# teensy-jst_01_2_v7.net
KiCad netlist of a schematic drawn in EAGLE
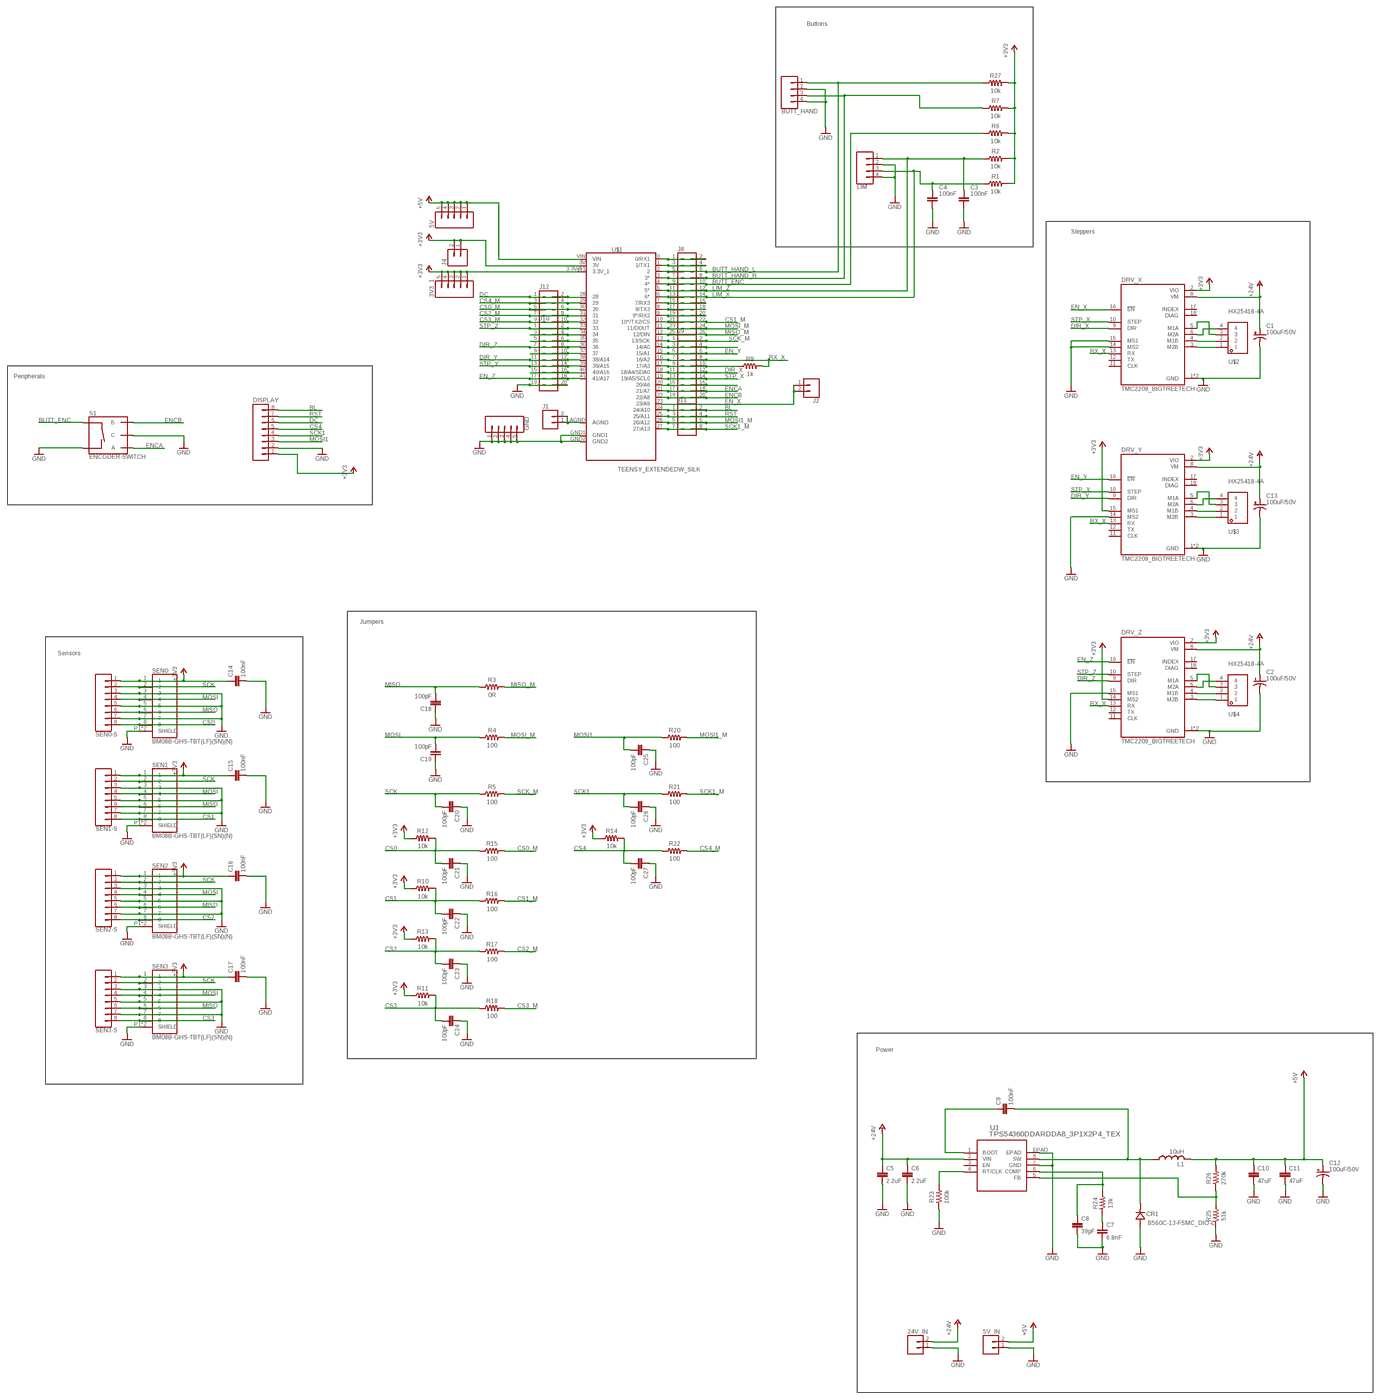
[diagram p0: schematic, sheet 1, overview]
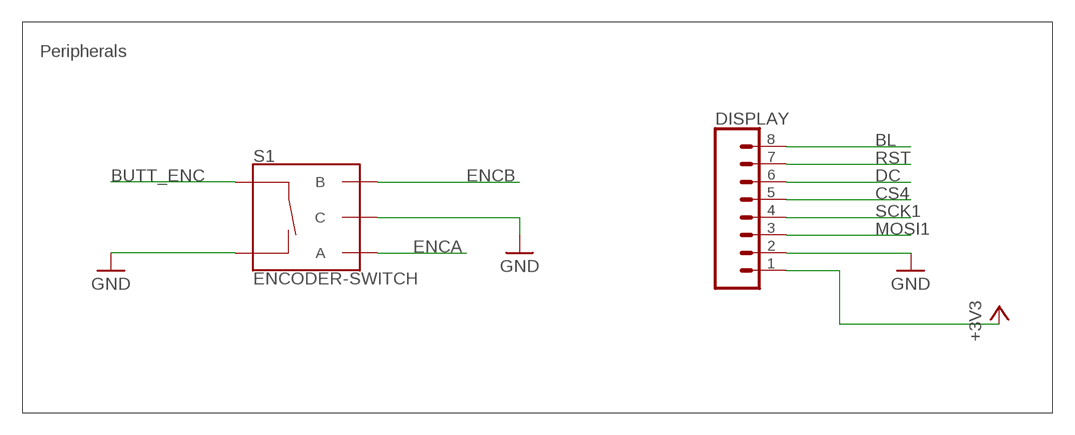
[diagram p1: schematic, sheet 1, part 1 of 4]
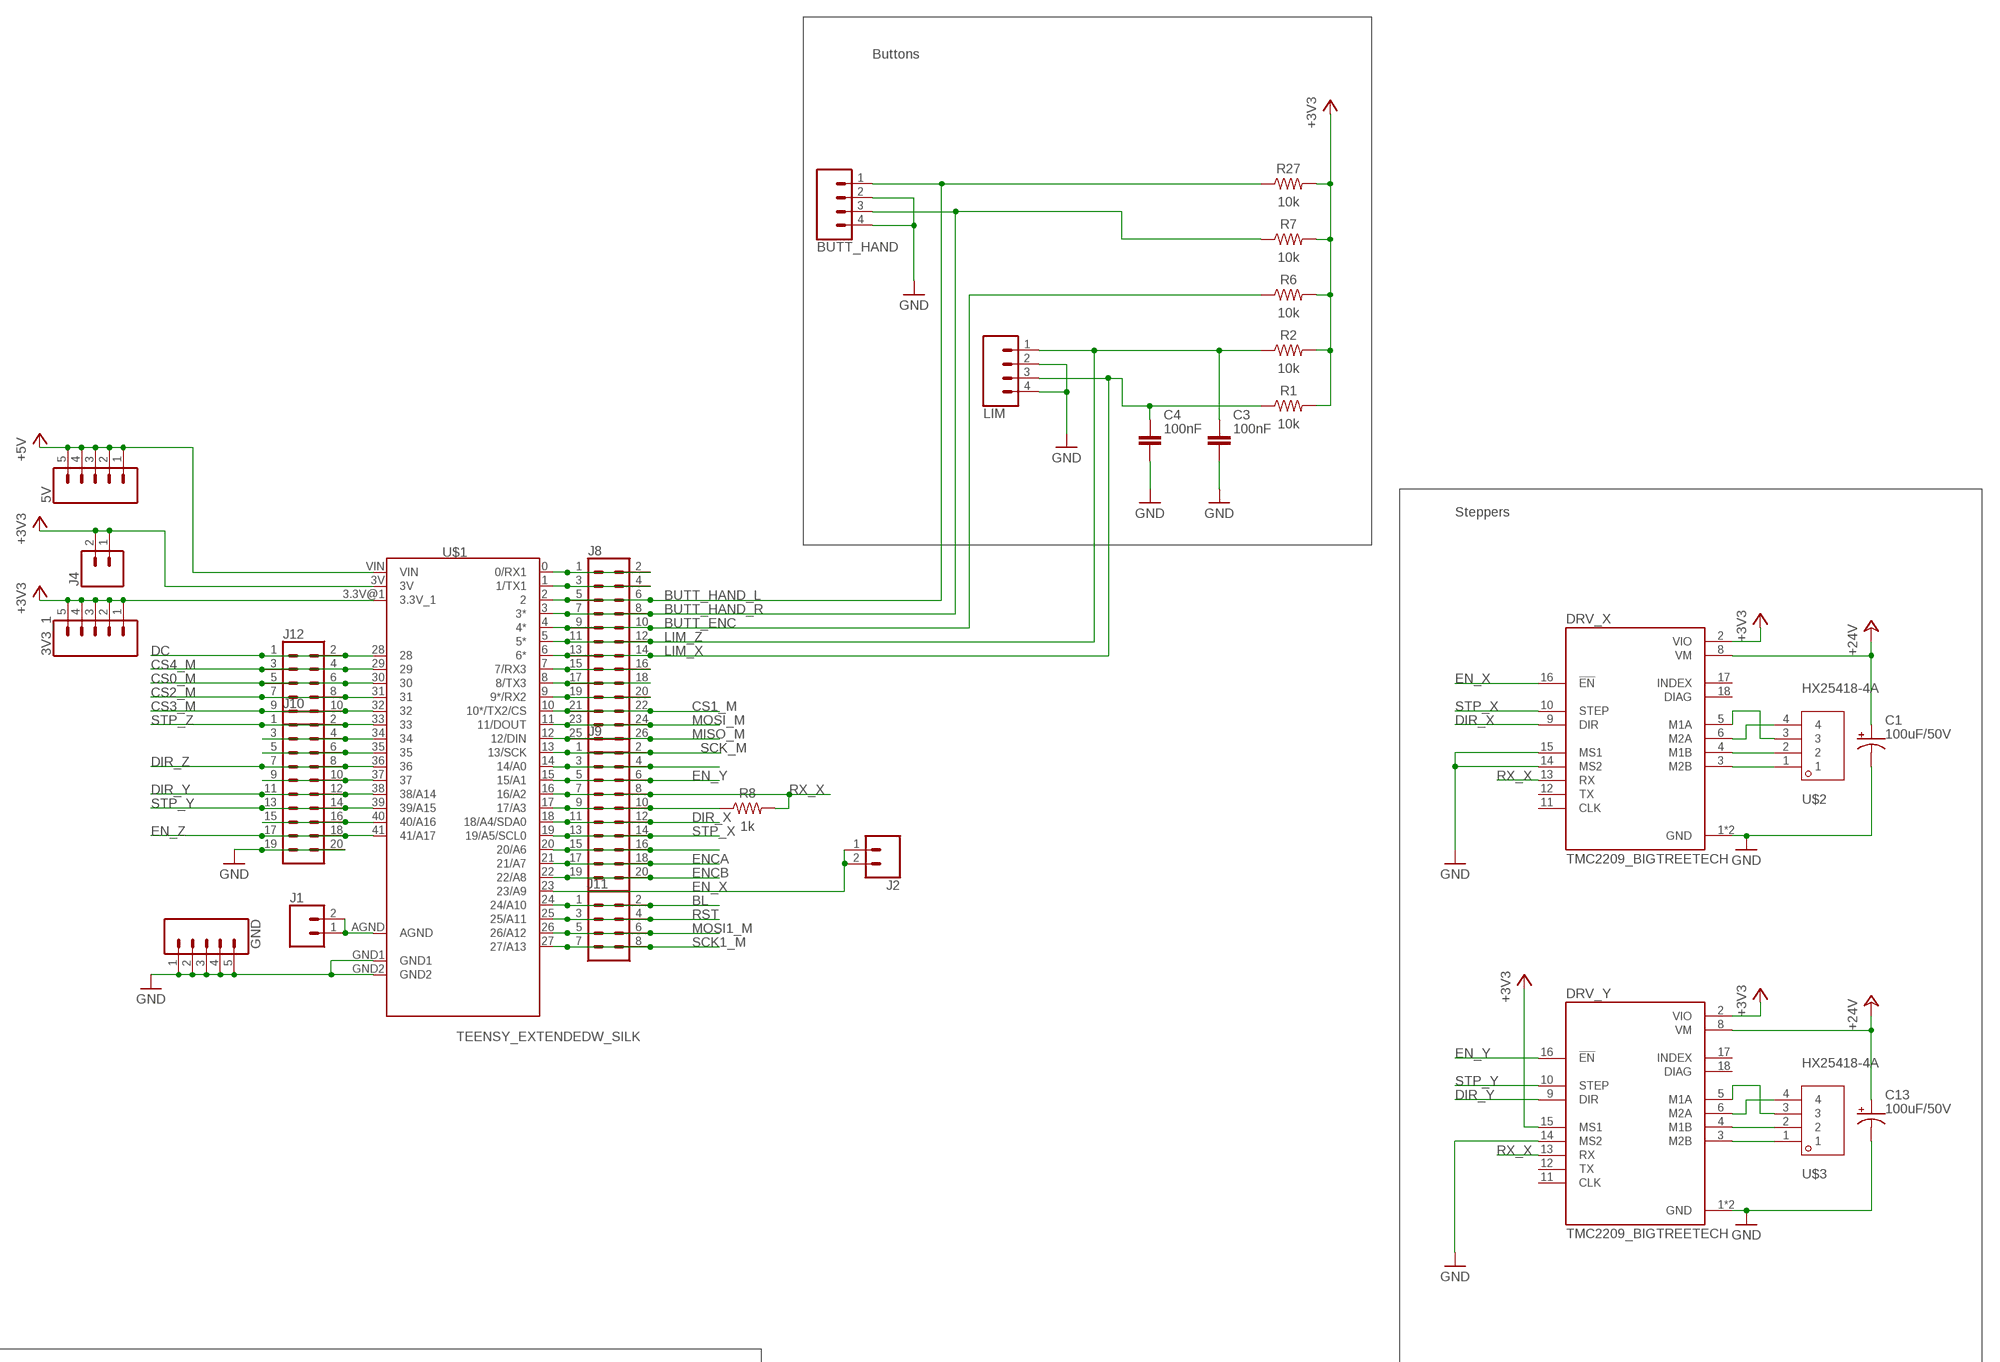
[diagram p2: schematic, sheet 1, part 2 of 4]
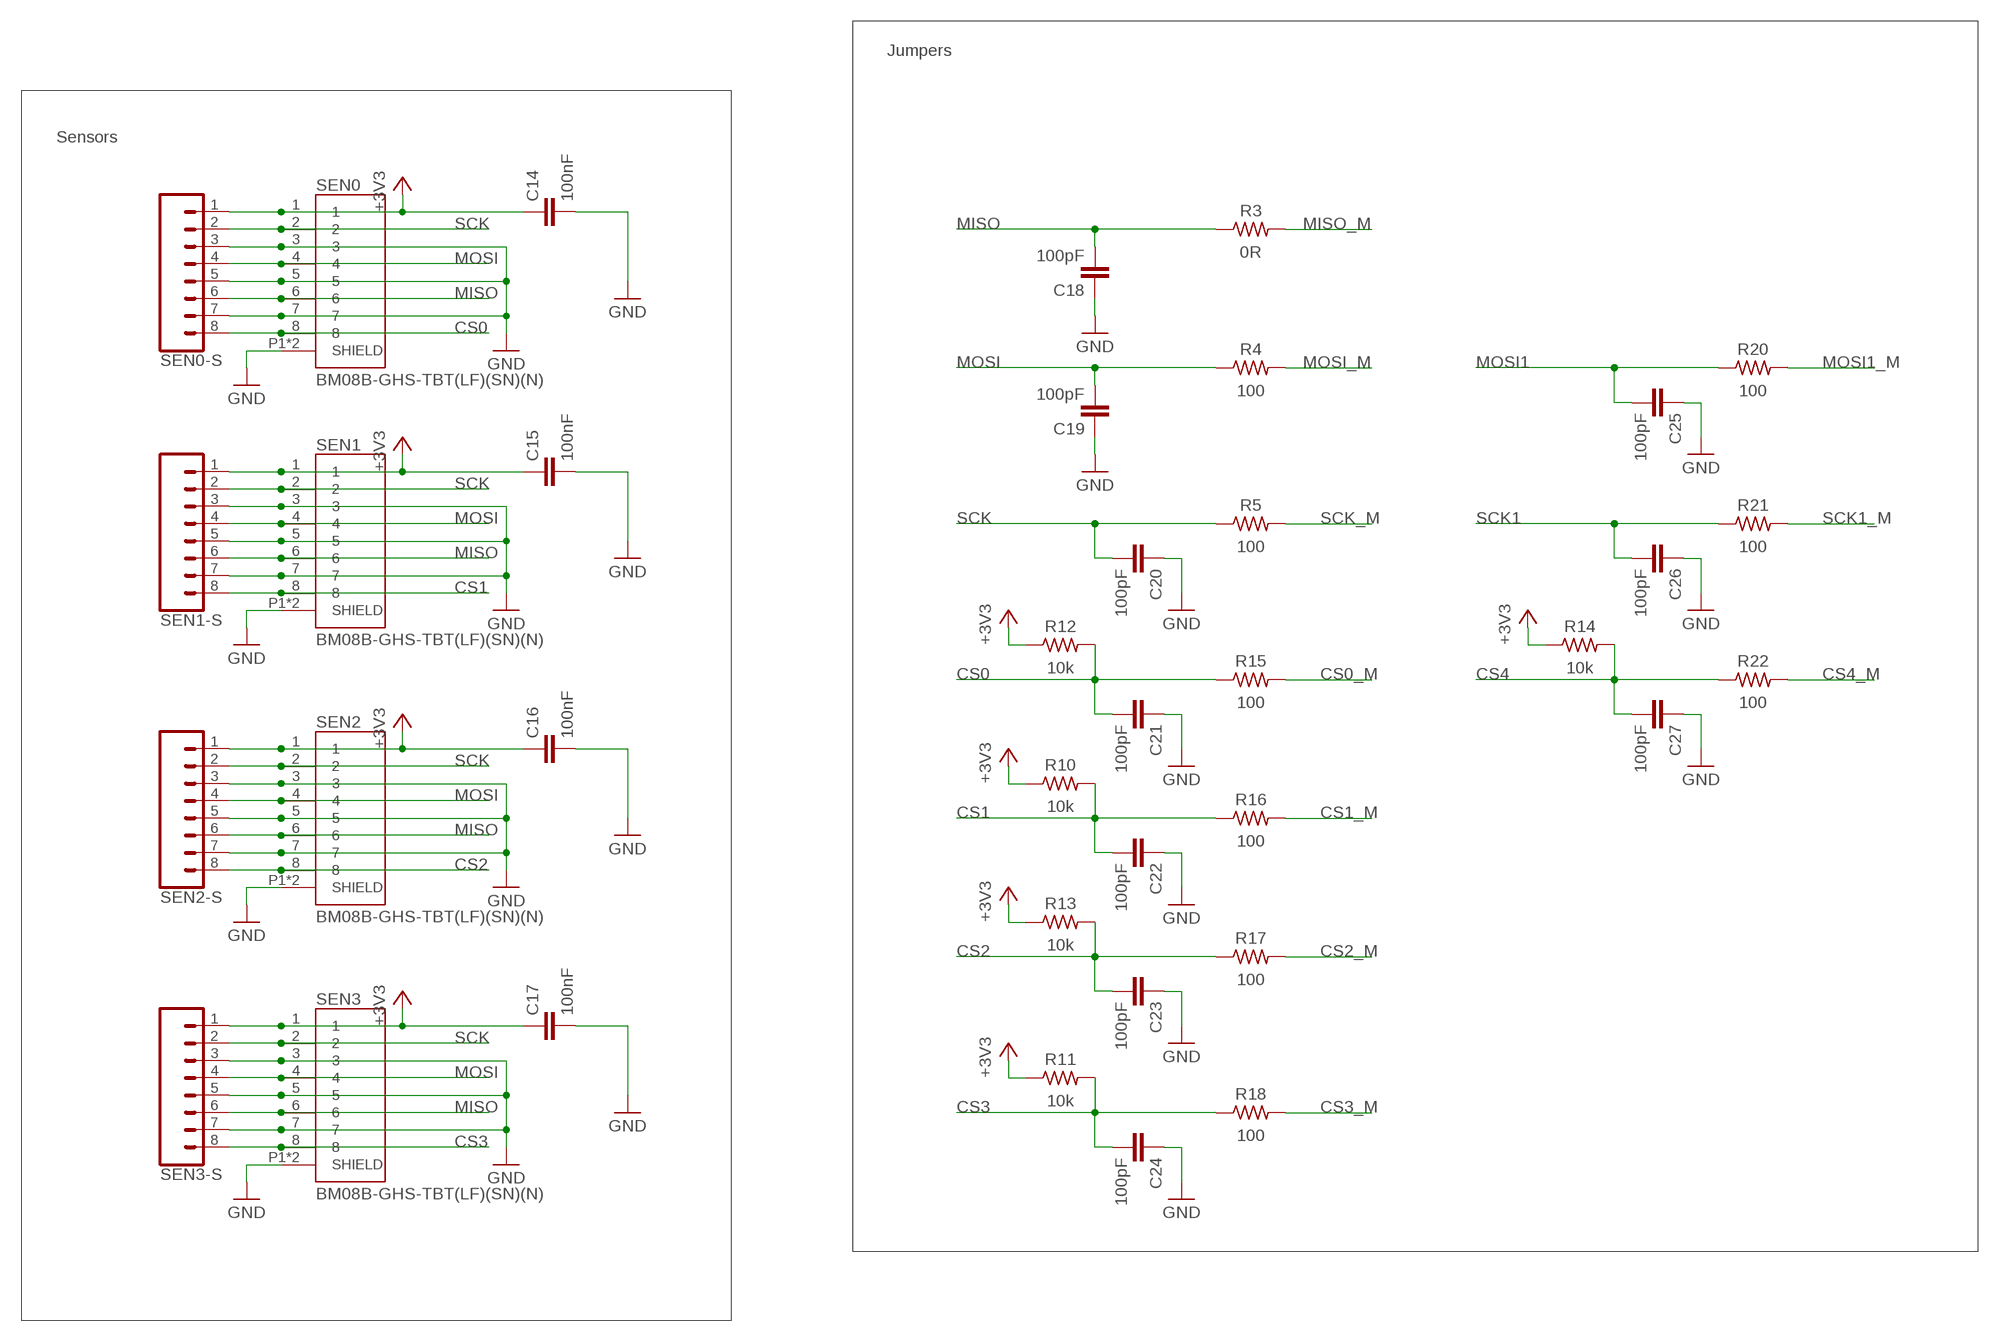
[diagram p3: schematic, sheet 1, part 3 of 4]
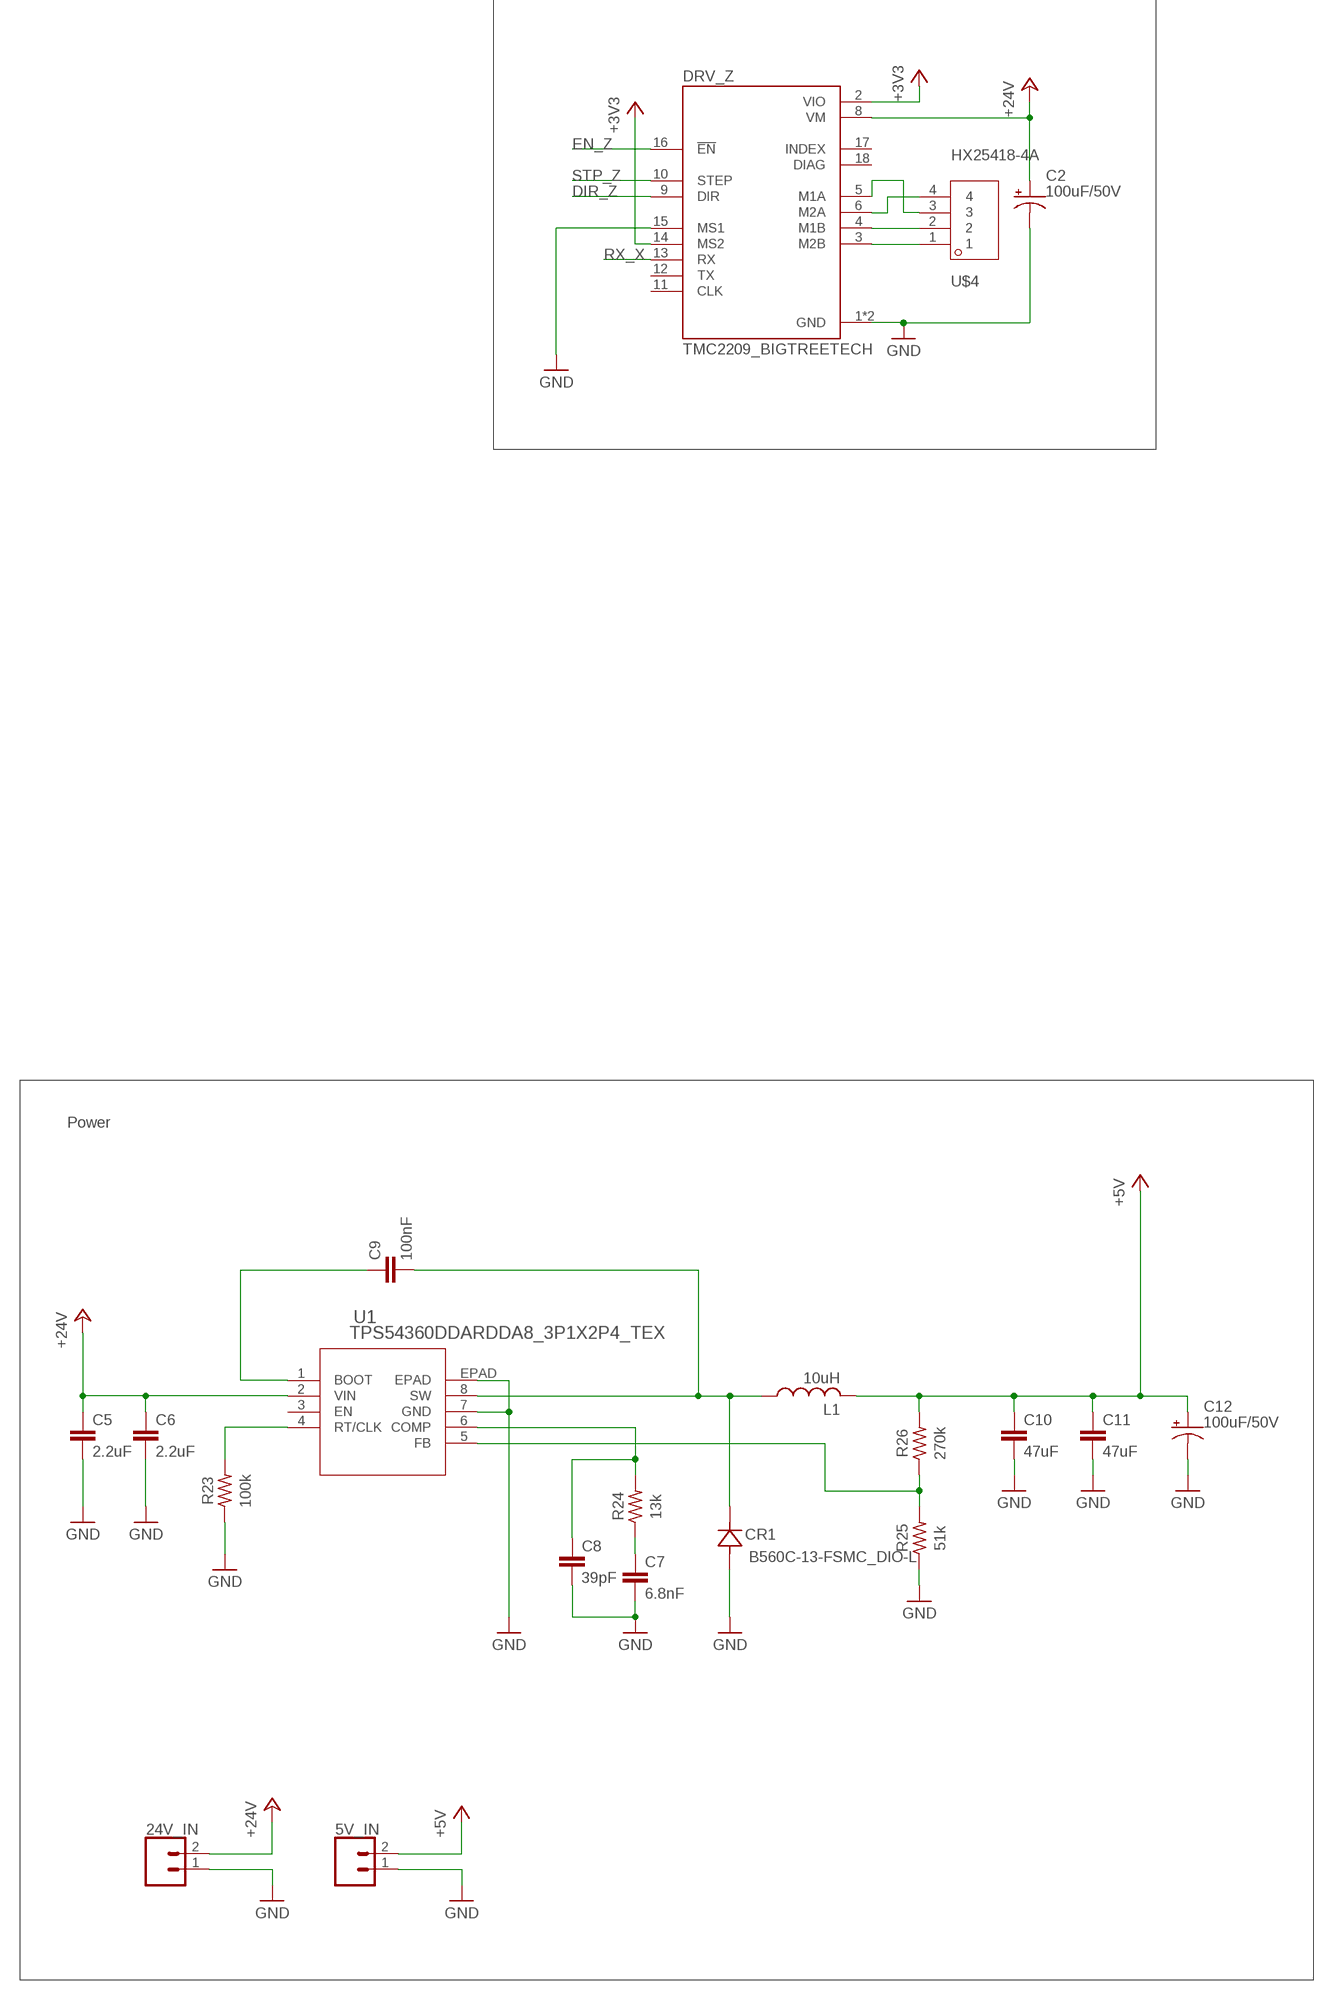
[diagram p4: schematic, sheet 1, part 4 of 4]

(export (version "E")
  (design (tool "Eeschema 10.0.6"))
  (components
    (comp (ref "3V3_1")
      (value "CONN_05PTH")
      (footprint "eagle-import:1X05")
      (libsource (lib "eagle-import") (part "CONN_05PTH"))
    )
    (comp (ref "5V")
      (value "CONN_05PTH")
      (footprint "eagle-import:1X05")
      (libsource (lib "eagle-import") (part "CONN_05PTH"))
    )
    (comp (ref "5V_IN")
      (value "CONN_025MM")
      (footprint "eagle-import:SCREWTERMINAL-5MM-2")
      (libsource (lib "eagle-import") (part "CONN_025MM"))
    )
    (comp (ref "24V_IN")
      (value "CONN_025MM")
      (footprint "eagle-import:SCREWTERMINAL-5MM-2")
      (libsource (lib "eagle-import") (part "CONN_025MM"))
    )
    (comp (ref "BUTT_HAND")
      (value "CONN_041X04_NO_SILK")
      (footprint "eagle-import:1X04_NO_SILK")
      (libsource (lib "eagle-import") (part "CONN_041X04_NO_SILK"))
    )
    (comp (ref "C1")
      (value "100uF/50V")
      (footprint "eagle-import:PANASONIC_D")
      (libsource (lib "eagle-import") (part "CPOL-USD"))
    )
    (comp (ref "C2")
      (value "100uF/50V")
      (footprint "eagle-import:PANASONIC_D")
      (libsource (lib "eagle-import") (part "CPOL-USD"))
    )
    (comp (ref "C3")
      (value "100nF")
      (footprint "eagle-import:C0603")
      (libsource (lib "eagle-import") (part "C-EUC0603"))
    )
    (comp (ref "C4")
      (value "100nF")
      (footprint "eagle-import:C0603")
      (libsource (lib "eagle-import") (part "C-EUC0603"))
    )
    (comp (ref "C5")
      (value "2.2uF")
      (footprint "eagle-import:C0603")
      (libsource (lib "eagle-import") (part "C-EUC0603"))
    )
    (comp (ref "C6")
      (value "2.2uF")
      (footprint "eagle-import:C0603")
      (libsource (lib "eagle-import") (part "C-EUC0603"))
    )
    (comp (ref "C7")
      (value "6.8nF")
      (footprint "eagle-import:C0402")
      (libsource (lib "eagle-import") (part "C-EUC0402"))
    )
    (comp (ref "C8")
      (value "39pF")
      (footprint "eagle-import:C0402")
      (libsource (lib "eagle-import") (part "C-EUC0402"))
    )
    (comp (ref "C9")
      (value "100nF")
      (footprint "eagle-import:C0402")
      (libsource (lib "eagle-import") (part "C-EUC0402"))
    )
    (comp (ref "C10")
      (value "47uF")
      (footprint "eagle-import:C0603")
      (libsource (lib "eagle-import") (part "C-EUC0603"))
    )
    (comp (ref "C11")
      (value "47uF")
      (footprint "eagle-import:C0603")
      (libsource (lib "eagle-import") (part "C-EUC0603"))
    )
    (comp (ref "C12")
      (value "100uF/50V")
      (footprint "eagle-import:PANASONIC_D")
      (libsource (lib "eagle-import") (part "CPOL-USD"))
    )
    (comp (ref "C13")
      (value "100uF/50V")
      (footprint "eagle-import:PANASONIC_D")
      (libsource (lib "eagle-import") (part "CPOL-USD"))
    )
    (comp (ref "C14")
      (value "100nF")
      (footprint "eagle-import:C0402")
      (libsource (lib "eagle-import") (part "C-EUC0402"))
    )
    (comp (ref "C15")
      (value "100nF")
      (footprint "eagle-import:C0402")
      (libsource (lib "eagle-import") (part "C-EUC0402"))
    )
    (comp (ref "C16")
      (value "100nF")
      (footprint "eagle-import:C0402")
      (libsource (lib "eagle-import") (part "C-EUC0402"))
    )
    (comp (ref "C17")
      (value "100nF")
      (footprint "eagle-import:C0402")
      (libsource (lib "eagle-import") (part "C-EUC0402"))
    )
    (comp (ref "C18")
      (value "100pF")
      (footprint "eagle-import:C0402K")
      (libsource (lib "eagle-import") (part "C-EUC0402K"))
    )
    (comp (ref "C19")
      (value "100pF")
      (footprint "eagle-import:C0402K")
      (libsource (lib "eagle-import") (part "C-EUC0402K"))
    )
    (comp (ref "C20")
      (value "100pF")
      (footprint "eagle-import:C0402K")
      (libsource (lib "eagle-import") (part "C-EUC0402K"))
    )
    (comp (ref "C21")
      (value "100pF")
      (footprint "eagle-import:C0402K")
      (libsource (lib "eagle-import") (part "C-EUC0402K"))
    )
    (comp (ref "C22")
      (value "100pF")
      (footprint "eagle-import:C0402")
      (libsource (lib "eagle-import") (part "C-EUC0402"))
    )
    (comp (ref "C23")
      (value "100pF")
      (footprint "eagle-import:C0402K")
      (libsource (lib "eagle-import") (part "C-EUC0402K"))
    )
    (comp (ref "C24")
      (value "100pF")
      (footprint "eagle-import:C0402K")
      (libsource (lib "eagle-import") (part "C-EUC0402K"))
    )
    (comp (ref "C25")
      (value "100pF")
      (footprint "eagle-import:C0402K")
      (libsource (lib "eagle-import") (part "C-EUC0402K"))
    )
    (comp (ref "C26")
      (value "100pF")
      (footprint "eagle-import:C0402K")
      (libsource (lib "eagle-import") (part "C-EUC0402K"))
    )
    (comp (ref "C27")
      (value "100pF")
      (footprint "eagle-import:C0402K")
      (libsource (lib "eagle-import") (part "C-EUC0402K"))
    )
    (comp (ref "CR1")
      (value "B560C-13-FSMC_DIO-L")
      (footprint "eagle-import:SMC_DIO-L")
      (fields
        (field (name "MANUFACTURER_PART_NUMBER") "B560C-13-F")
        (field (name "COPYRIGHT") "Copyright (C) 2024 Ultra Librarian. All rights reserved.")
      )
      (libsource (lib "eagle-import") (part "B560C-13-FSMC_DIO-L"))
    )
    (comp (ref "DISPLAY")
      (value "CONN_08\"")
      (footprint "eagle-import:1X08")
      (libsource (lib "eagle-import") (part "CONN_08{dblquote}"))
    )
    (comp (ref "DRV_X")
      (value "TMC2209_BIGTREETECH")
      (footprint "eagle-import:MODULE_TMC2209_BIGTREETECH")
      (fields
        (field (name "MF") "Trinamic Motion Control GmbH")
        (field (name "MP") "TMC2209 SILENTSTEPSTICK")
      )
      (libsource (lib "eagle-import") (part "TMC2209_BIGTREETECH"))
    )
    (comp (ref "DRV_Y")
      (value "TMC2209_BIGTREETECH")
      (footprint "eagle-import:MODULE_TMC2209_BIGTREETECH")
      (fields
        (field (name "MF") "Trinamic Motion Control GmbH")
        (field (name "MP") "TMC2209 SILENTSTEPSTICK")
      )
      (libsource (lib "eagle-import") (part "TMC2209_BIGTREETECH"))
    )
    (comp (ref "DRV_Z")
      (value "TMC2209_BIGTREETECH")
      (footprint "eagle-import:MODULE_TMC2209_BIGTREETECH")
      (fields
        (field (name "MF") "Trinamic Motion Control GmbH")
        (field (name "MP") "TMC2209 SILENTSTEPSTICK")
      )
      (libsource (lib "eagle-import") (part "TMC2209_BIGTREETECH"))
    )
    (comp (ref "GND")
      (value "CONN_05PTH")
      (footprint "eagle-import:1X05")
      (libsource (lib "eagle-import") (part "CONN_05PTH"))
    )
    (comp (ref "J1")
      (value "CONN_02")
      (footprint "eagle-import:1X02")
      (libsource (lib "eagle-import") (part "CONN_02"))
    )
    (comp (ref "J2")
      (value "CONN_02")
      (footprint "eagle-import:1X02")
      (libsource (lib "eagle-import") (part "CONN_02"))
    )
    (comp (ref "J4")
      (value "CONN_02")
      (footprint "eagle-import:1X02")
      (libsource (lib "eagle-import") (part "CONN_02"))
    )
    (comp (ref "J8")
      (value "CONN_13X22X13")
      (footprint "eagle-import:2X13")
      (libsource (lib "eagle-import") (part "CONN_13X22X13"))
    )
    (comp (ref "J9")
      (value "CONN_10X2")
      (footprint "eagle-import:2X10")
      (libsource (lib "eagle-import") (part "CONN_10X2"))
    )
    (comp (ref "J10")
      (value "CONN_10X2")
      (footprint "eagle-import:2X10")
      (libsource (lib "eagle-import") (part "CONN_10X2"))
    )
    (comp (ref "J11")
      (value "CONN_04X2")
      (footprint "eagle-import:2X4")
      (libsource (lib "eagle-import") (part "CONN_04X2"))
    )
    (comp (ref "J12")
      (value "CONN_05X2PTH")
      (footprint "eagle-import:2X5")
      (libsource (lib "eagle-import") (part "CONN_05X2PTH"))
    )
    (comp (ref "L1")
      (value "10uH")
      (footprint "eagle-import:MWSA0503S-100MT")
      (libsource (lib "eagle-import") (part "L-USMWSA0503S-100MT"))
    )
    (comp (ref "LIM")
      (value "CONN_041X04_NO_SILK")
      (footprint "eagle-import:1X04_NO_SILK")
      (libsource (lib "eagle-import") (part "CONN_041X04_NO_SILK"))
    )
    (comp (ref "R1")
      (value "10k")
      (footprint "eagle-import:RESC1608X60")
      (libsource (lib "eagle-import") (part "R-USCHIP-0603(1608-METRIC)_"))
    )
    (comp (ref "R2")
      (value "10k")
      (footprint "eagle-import:RESC1608X60")
      (libsource (lib "eagle-import") (part "R-USCHIP-0603(1608-METRIC)_"))
    )
    (comp (ref "R3")
      (value "0R")
      (footprint "eagle-import:RESC1608X60")
      (libsource (lib "eagle-import") (part "R-USCHIP-0603(1608-METRIC)_"))
    )
    (comp (ref "R4")
      (value "100")
      (footprint "eagle-import:RESC1608X60")
      (libsource (lib "eagle-import") (part "R-USCHIP-0603(1608-METRIC)_"))
    )
    (comp (ref "R5")
      (value "100")
      (footprint "eagle-import:RESC1608X60")
      (libsource (lib "eagle-import") (part "R-USCHIP-0603(1608-METRIC)_"))
    )
    (comp (ref "R6")
      (value "10k")
      (footprint "eagle-import:RESC1608X60")
      (libsource (lib "eagle-import") (part "R-USCHIP-0603(1608-METRIC)_"))
    )
    (comp (ref "R7")
      (value "10k")
      (footprint "eagle-import:RESC1608X60")
      (libsource (lib "eagle-import") (part "R-USCHIP-0603(1608-METRIC)_"))
    )
    (comp (ref "R8")
      (value "1k")
      (footprint "eagle-import:RESC1608X60")
      (libsource (lib "eagle-import") (part "R-USCHIP-0603(1608-METRIC)_"))
    )
    (comp (ref "R10")
      (value "10k")
      (footprint "eagle-import:RESC1608X60")
      (libsource (lib "eagle-import") (part "R-USCHIP-0603(1608-METRIC)_"))
    )
    (comp (ref "R11")
      (value "10k")
      (footprint "eagle-import:RESC1608X60")
      (libsource (lib "eagle-import") (part "R-USCHIP-0603(1608-METRIC)_"))
    )
    (comp (ref "R12")
      (value "10k")
      (footprint "eagle-import:RESC1608X60")
      (libsource (lib "eagle-import") (part "R-USCHIP-0603(1608-METRIC)_"))
    )
    (comp (ref "R13")
      (value "10k")
      (footprint "eagle-import:RESC1608X60")
      (libsource (lib "eagle-import") (part "R-USCHIP-0603(1608-METRIC)_"))
    )
    (comp (ref "R14")
      (value "10k")
      (footprint "eagle-import:RESC1608X60")
      (libsource (lib "eagle-import") (part "R-USCHIP-0603(1608-METRIC)_"))
    )
    (comp (ref "R15")
      (value "100")
      (footprint "eagle-import:RESC1608X60")
      (libsource (lib "eagle-import") (part "R-USCHIP-0603(1608-METRIC)_"))
    )
    (comp (ref "R16")
      (value "100")
      (footprint "eagle-import:RESC1608X60")
      (libsource (lib "eagle-import") (part "R-USCHIP-0603(1608-METRIC)_"))
    )
    (comp (ref "R17")
      (value "100")
      (footprint "eagle-import:RESC1608X60")
      (libsource (lib "eagle-import") (part "R-USCHIP-0603(1608-METRIC)_"))
    )
    (comp (ref "R18")
      (value "100")
      (footprint "eagle-import:RESC1608X60")
      (libsource (lib "eagle-import") (part "R-USCHIP-0603(1608-METRIC)_"))
    )
    (comp (ref "R20")
      (value "100")
      (footprint "eagle-import:RESC1608X60")
      (libsource (lib "eagle-import") (part "R-USCHIP-0603(1608-METRIC)_"))
    )
    (comp (ref "R21")
      (value "100")
      (footprint "eagle-import:RESC1608X60")
      (libsource (lib "eagle-import") (part "R-USCHIP-0603(1608-METRIC)_"))
    )
    (comp (ref "R22")
      (value "100")
      (footprint "eagle-import:RESC1608X60")
      (libsource (lib "eagle-import") (part "R-USCHIP-0603(1608-METRIC)_"))
    )
    (comp (ref "R23")
      (value "100k")
      (footprint "eagle-import:RESC1005X40")
      (libsource (lib "eagle-import") (part "R-USCHIP-0402(1005-METRIC)_"))
    )
    (comp (ref "R24")
      (value "13k")
      (footprint "eagle-import:RESC1005X40")
      (libsource (lib "eagle-import") (part "R-USCHIP-0402(1005-METRIC)_"))
    )
    (comp (ref "R25")
      (value "51k")
      (footprint "eagle-import:RESC1005X40")
      (libsource (lib "eagle-import") (part "R-USCHIP-0402(1005-METRIC)_"))
    )
    (comp (ref "R26")
      (value "270k")
      (footprint "eagle-import:RESC1005X40")
      (libsource (lib "eagle-import") (part "R-USCHIP-0402(1005-METRIC)_"))
    )
    (comp (ref "R27")
      (value "10k")
      (footprint "eagle-import:RESC1608X60")
      (libsource (lib "eagle-import") (part "R-USCHIP-0603(1608-METRIC)_"))
    )
    (comp (ref "S1")
      (value "ENCODER-SWITCH")
      (footprint "eagle-import:ROTARY_ENC_PLAIN")
      (libsource (lib "eagle-import") (part "ENCODER-SWITCH"))
    )
    (comp (ref "SEN0")
      (value "BM08B-GHS-TBT(LF)(SN)(N)")
      (footprint "eagle-import:JST_BM08B-GHS-TBT(LF)(SN)(N)")
      (fields (field (name "MF") "JST Sales"))
      (libsource (lib "eagle-import") (part "BM08B-GHS-TBT(LF)(SN)(N)"))
    )
    (comp (ref "SEN0-S")
      (value "CONN_08\"")
      (footprint "eagle-import:1X08")
      (libsource (lib "eagle-import") (part "CONN_08{dblquote}"))
    )
    (comp (ref "SEN1")
      (value "BM08B-GHS-TBT(LF)(SN)(N)")
      (footprint "eagle-import:JST_BM08B-GHS-TBT(LF)(SN)(N)")
      (fields (field (name "MF") "JST Sales"))
      (libsource (lib "eagle-import") (part "BM08B-GHS-TBT(LF)(SN)(N)"))
    )
    (comp (ref "SEN1-S")
      (value "CONN_08\"")
      (footprint "eagle-import:1X08")
      (libsource (lib "eagle-import") (part "CONN_08{dblquote}"))
    )
    (comp (ref "SEN2")
      (value "BM08B-GHS-TBT(LF)(SN)(N)")
      (footprint "eagle-import:JST_BM08B-GHS-TBT(LF)(SN)(N)")
      (fields (field (name "MF") "JST Sales"))
      (libsource (lib "eagle-import") (part "BM08B-GHS-TBT(LF)(SN)(N)"))
    )
    (comp (ref "SEN2-S")
      (value "CONN_08\"")
      (footprint "eagle-import:1X08")
      (libsource (lib "eagle-import") (part "CONN_08{dblquote}"))
    )
    (comp (ref "SEN3")
      (value "BM08B-GHS-TBT(LF)(SN)(N)")
      (footprint "eagle-import:JST_BM08B-GHS-TBT(LF)(SN)(N)")
      (fields (field (name "MF") "JST Sales"))
      (libsource (lib "eagle-import") (part "BM08B-GHS-TBT(LF)(SN)(N)"))
    )
    (comp (ref "SEN3-S")
      (value "CONN_08\"")
      (footprint "eagle-import:1X08")
      (libsource (lib "eagle-import") (part "CONN_08{dblquote}"))
    )
    (comp (ref "U$1")
      (value "TEENSY_EXTENDEDW_SILK")
      (footprint "eagle-import:TEENSY_EXTENDED")
      (libsource (lib "eagle-import") (part "TEENSY_EXTENDEDW_SILK"))
    )
    (comp (ref "U$2")
      (value "HX25418-4A")
      (footprint "eagle-import:HX25418-4A")
      (libsource (lib "eagle-import") (part "HX25418-4A"))
    )
    (comp (ref "U$3")
      (value "HX25418-4A")
      (footprint "eagle-import:HX25418-4A")
      (libsource (lib "eagle-import") (part "HX25418-4A"))
    )
    (comp (ref "U$4")
      (value "HX25418-4A")
      (footprint "eagle-import:HX25418-4A")
      (libsource (lib "eagle-import") (part "HX25418-4A"))
    )
    (comp (ref "U1")
      (value "TPS54360DDARDDA8_3P1X2P4_TEX")
      (footprint "eagle-import:DDA8_3P1X2P4_TEX")
      (fields
        (field (name "MANUFACTURER_PART_NUMBER") "TPS54360DDAR")
        (field (name "COPYRIGHT") "Copyright (C) 2024 Ultra Librarian. All rights reserved.")
      )
      (libsource (lib "eagle-import") (part "TPS54360DDARDDA8_3P1X2P4_TEX"))
    )
  )
  (nets
    (net (code "1") (name "+3V3") (class "Default")
      (node (ref "3V3_1") (pin "1") (pinfunction "1_1") (pintype "passive"))
      (node (ref "3V3_1") (pin "2") (pinfunction "2_2") (pintype "passive"))
      (node (ref "3V3_1") (pin "3") (pinfunction "3_3") (pintype "passive"))
      (node (ref "3V3_1") (pin "4") (pinfunction "4_4") (pintype "passive"))
      (node (ref "3V3_1") (pin "5") (pinfunction "5_5") (pintype "passive"))
      (node (ref "C14") (pin "1") (pinfunction "1_1") (pintype "passive"))
      (node (ref "C15") (pin "1") (pinfunction "1_1") (pintype "passive"))
      (node (ref "C16") (pin "1") (pinfunction "1_1") (pintype "passive"))
      (node (ref "C17") (pin "1") (pinfunction "1_1") (pintype "passive"))
      (node (ref "DISPLAY") (pin "1") (pinfunction "1_1") (pintype "passive"))
      (node (ref "DRV_X") (pin "2") (pinfunction "VIO_2") (pintype "power_in"))
      (node (ref "DRV_Y") (pin "15") (pinfunction "MS1_15") (pintype "input"))
      (node (ref "DRV_Y") (pin "2") (pinfunction "VIO_2") (pintype "power_in"))
      (node (ref "DRV_Z") (pin "14") (pinfunction "MS2_14") (pintype "input"))
      (node (ref "DRV_Z") (pin "2") (pinfunction "VIO_2") (pintype "power_in"))
      (node (ref "J4") (pin "1") (pinfunction "1_1") (pintype "passive"))
      (node (ref "J4") (pin "2") (pinfunction "2_2") (pintype "passive"))
      (node (ref "R1") (pin "2") (pinfunction "2_2") (pintype "passive"))
      (node (ref "R10") (pin "1") (pinfunction "1_1") (pintype "passive"))
      (node (ref "R11") (pin "1") (pinfunction "1_1") (pintype "passive"))
      (node (ref "R12") (pin "1") (pinfunction "1_1") (pintype "passive"))
      (node (ref "R13") (pin "1") (pinfunction "1_1") (pintype "passive"))
      (node (ref "R14") (pin "1") (pinfunction "1_1") (pintype "passive"))
      (node (ref "R2") (pin "2") (pinfunction "2_2") (pintype "passive"))
      (node (ref "R27") (pin "2") (pinfunction "2_2") (pintype "passive"))
      (node (ref "R6") (pin "2") (pinfunction "2_2") (pintype "passive"))
      (node (ref "R7") (pin "2") (pinfunction "2_2") (pintype "passive"))
      (node (ref "SEN0") (pin "1") (pinfunction "1_1") (pintype "passive"))
      (node (ref "SEN0-S") (pin "1") (pinfunction "1_1") (pintype "passive"))
      (node (ref "SEN1") (pin "1") (pinfunction "1_1") (pintype "passive"))
      (node (ref "SEN1-S") (pin "1") (pinfunction "1_1") (pintype "passive"))
      (node (ref "SEN2") (pin "1") (pinfunction "1_1") (pintype "passive"))
      (node (ref "SEN2-S") (pin "1") (pinfunction "1_1") (pintype "passive"))
      (node (ref "SEN3") (pin "1") (pinfunction "1_1") (pintype "passive"))
      (node (ref "SEN3-S") (pin "1") (pinfunction "1_1") (pintype "passive"))
      (node (ref "U$1") (pin "3.3V@1") (pinfunction "3.3V_1_3.3V@1") (pintype "power_in"))
      (node (ref "U$1") (pin "3V") (pinfunction "3V_3V") (pintype "power_in"))
    )
    (net (code "2") (name "+5V") (class "Default")
      (node (ref "5V") (pin "1") (pinfunction "1_1") (pintype "passive"))
      (node (ref "5V") (pin "2") (pinfunction "2_2") (pintype "passive"))
      (node (ref "5V") (pin "3") (pinfunction "3_3") (pintype "passive"))
      (node (ref "5V") (pin "4") (pinfunction "4_4") (pintype "passive"))
      (node (ref "5V") (pin "5") (pinfunction "5_5") (pintype "passive"))
      (node (ref "5V_IN") (pin "2") (pinfunction "2_2") (pintype "passive"))
      (node (ref "C10") (pin "1") (pinfunction "1_1") (pintype "passive"))
      (node (ref "C11") (pin "1") (pinfunction "1_1") (pintype "passive"))
      (node (ref "C12") (pin "+") (pinfunction "+_+") (pintype "passive"))
      (node (ref "L1") (pin "2") (pinfunction "2_2") (pintype "passive"))
      (node (ref "R26") (pin "2") (pinfunction "2_2") (pintype "passive"))
      (node (ref "U$1") (pin "VIN") (pinfunction "VIN_VIN") (pintype "power_in"))
    )
    (net (code "3") (name "+24V") (class "Default")
      (node (ref "24V_IN") (pin "2") (pinfunction "2_2") (pintype "passive"))
      (node (ref "C1") (pin "+") (pinfunction "+_+") (pintype "passive"))
      (node (ref "C13") (pin "+") (pinfunction "+_+") (pintype "passive"))
      (node (ref "C2") (pin "+") (pinfunction "+_+") (pintype "passive"))
      (node (ref "C5") (pin "1") (pinfunction "1_1") (pintype "passive"))
      (node (ref "C6") (pin "1") (pinfunction "1_1") (pintype "passive"))
      (node (ref "DRV_X") (pin "8") (pinfunction "VM_8") (pintype "power_in"))
      (node (ref "DRV_Y") (pin "8") (pinfunction "VM_8") (pintype "power_in"))
      (node (ref "DRV_Z") (pin "8") (pinfunction "VM_8") (pintype "power_in"))
      (node (ref "U1") (pin "2") (pinfunction "VIN_2") (pintype "input"))
    )
    (net (code "4") (name "/BL") (class "Default")
      (node (ref "DISPLAY") (pin "8") (pinfunction "8_8") (pintype "passive"))
      (node (ref "J11") (pin "1") (pinfunction "1_1") (pintype "passive"))
      (node (ref "J11") (pin "2") (pinfunction "2_2") (pintype "passive"))
      (node (ref "U$1") (pin "24") (pinfunction "24/A10_24") (pintype "bidirectional"))
    )
    (net (code "5") (name "/BUTT_ENC") (class "Default")
      (node (ref "J8") (pin "10") (pinfunction "10_10") (pintype "passive"))
      (node (ref "J8") (pin "9") (pinfunction "9_9") (pintype "passive"))
      (node (ref "R6") (pin "1") (pinfunction "1_1") (pintype "passive"))
      (node (ref "S1") (pin "SW+") (pinfunction "SW+_SW+") (pintype "bidirectional"))
      (node (ref "U$1") (pin "4") (pinfunction "4*_4") (pintype "bidirectional"))
    )
    (net (code "6") (name "/BUTT_HAND_L") (class "Default")
      (node (ref "BUTT_HAND") (pin "1") (pinfunction "1_1") (pintype "passive"))
      (node (ref "J8") (pin "5") (pinfunction "5_5") (pintype "passive"))
      (node (ref "J8") (pin "6") (pinfunction "6_6") (pintype "passive"))
      (node (ref "R27") (pin "1") (pinfunction "1_1") (pintype "passive"))
      (node (ref "U$1") (pin "2") (pinfunction "2_2") (pintype "bidirectional"))
    )
    (net (code "7") (name "/BUTT_HAND_R") (class "Default")
      (node (ref "BUTT_HAND") (pin "3") (pinfunction "3_3") (pintype "passive"))
      (node (ref "J8") (pin "7") (pinfunction "7_7") (pintype "passive"))
      (node (ref "J8") (pin "8") (pinfunction "8_8") (pintype "passive"))
      (node (ref "R7") (pin "1") (pinfunction "1_1") (pintype "passive"))
      (node (ref "U$1") (pin "3") (pinfunction "3*_3") (pintype "bidirectional"))
    )
    (net (code "8") (name "/CS0") (class "Default")
      (node (ref "C21") (pin "2") (pinfunction "2_2") (pintype "passive"))
      (node (ref "R12") (pin "2") (pinfunction "2_2") (pintype "passive"))
      (node (ref "R15") (pin "1") (pinfunction "1_1") (pintype "passive"))
      (node (ref "SEN0") (pin "8") (pinfunction "8_8") (pintype "passive"))
      (node (ref "SEN0-S") (pin "8") (pinfunction "8_8") (pintype "passive"))
    )
    (net (code "9") (name "/CS0_M") (class "Default")
      (node (ref "J12") (pin "5") (pinfunction "5_5") (pintype "passive"))
      (node (ref "J12") (pin "6") (pinfunction "6_6") (pintype "passive"))
      (node (ref "R15") (pin "2") (pinfunction "2_2") (pintype "passive"))
      (node (ref "U$1") (pin "30") (pinfunction "30_30") (pintype "bidirectional"))
    )
    (net (code "10") (name "/CS1") (class "Default")
      (node (ref "C22") (pin "2") (pinfunction "2_2") (pintype "passive"))
      (node (ref "R10") (pin "2") (pinfunction "2_2") (pintype "passive"))
      (node (ref "R16") (pin "1") (pinfunction "1_1") (pintype "passive"))
      (node (ref "SEN1") (pin "8") (pinfunction "8_8") (pintype "passive"))
      (node (ref "SEN1-S") (pin "8") (pinfunction "8_8") (pintype "passive"))
    )
    (net (code "11") (name "/CS1_M") (class "Default")
      (node (ref "J8") (pin "21") (pinfunction "21_21") (pintype "passive"))
      (node (ref "J8") (pin "22") (pinfunction "22_22") (pintype "passive"))
      (node (ref "R16") (pin "2") (pinfunction "2_2") (pintype "passive"))
      (node (ref "U$1") (pin "10") (pinfunction "10*/TX2/CS_10") (pintype "bidirectional"))
    )
    (net (code "12") (name "/CS2") (class "Default")
      (node (ref "C23") (pin "2") (pinfunction "2_2") (pintype "passive"))
      (node (ref "R13") (pin "2") (pinfunction "2_2") (pintype "passive"))
      (node (ref "R17") (pin "1") (pinfunction "1_1") (pintype "passive"))
      (node (ref "SEN2") (pin "8") (pinfunction "8_8") (pintype "passive"))
      (node (ref "SEN2-S") (pin "8") (pinfunction "8_8") (pintype "passive"))
    )
    (net (code "13") (name "/CS2_M") (class "Default")
      (node (ref "J12") (pin "7") (pinfunction "7_7") (pintype "passive"))
      (node (ref "J12") (pin "8") (pinfunction "8_8") (pintype "passive"))
      (node (ref "R17") (pin "2") (pinfunction "2_2") (pintype "passive"))
      (node (ref "U$1") (pin "31") (pinfunction "31_31") (pintype "bidirectional"))
    )
    (net (code "14") (name "/CS3") (class "Default")
      (node (ref "C24") (pin "2") (pinfunction "2_2") (pintype "passive"))
      (node (ref "R11") (pin "2") (pinfunction "2_2") (pintype "passive"))
      (node (ref "R18") (pin "1") (pinfunction "1_1") (pintype "passive"))
      (node (ref "SEN3") (pin "8") (pinfunction "8_8") (pintype "passive"))
      (node (ref "SEN3-S") (pin "8") (pinfunction "8_8") (pintype "passive"))
    )
    (net (code "15") (name "/CS3_M") (class "Default")
      (node (ref "J12") (pin "10") (pinfunction "10_10") (pintype "passive"))
      (node (ref "J12") (pin "9") (pinfunction "9_9") (pintype "passive"))
      (node (ref "R18") (pin "2") (pinfunction "2_2") (pintype "passive"))
      (node (ref "U$1") (pin "32") (pinfunction "32_32") (pintype "bidirectional"))
    )
    (net (code "16") (name "/CS4") (class "Default")
      (node (ref "C27") (pin "2") (pinfunction "2_2") (pintype "passive"))
      (node (ref "DISPLAY") (pin "5") (pinfunction "5_5") (pintype "passive"))
      (node (ref "R14") (pin "2") (pinfunction "2_2") (pintype "passive"))
      (node (ref "R22") (pin "1") (pinfunction "1_1") (pintype "passive"))
    )
    (net (code "17") (name "/CS4_M") (class "Default")
      (node (ref "J12") (pin "3") (pinfunction "3_3") (pintype "passive"))
      (node (ref "J12") (pin "4") (pinfunction "4_4") (pintype "passive"))
      (node (ref "R22") (pin "2") (pinfunction "2_2") (pintype "passive"))
      (node (ref "U$1") (pin "29") (pinfunction "29_29") (pintype "bidirectional"))
    )
    (net (code "18") (name "/DC") (class "Default")
      (node (ref "DISPLAY") (pin "6") (pinfunction "6_6") (pintype "passive"))
      (node (ref "J12") (pin "1") (pinfunction "1_1") (pintype "passive"))
      (node (ref "J12") (pin "2") (pinfunction "2_2") (pintype "passive"))
      (node (ref "U$1") (pin "28") (pinfunction "28_28") (pintype "bidirectional"))
    )
    (net (code "19") (name "/DIR_X") (class "Default")
      (node (ref "DRV_X") (pin "9") (pinfunction "DIR_9") (pintype "input"))
      (node (ref "J9") (pin "11") (pinfunction "11_11") (pintype "passive"))
      (node (ref "J9") (pin "12") (pinfunction "12_12") (pintype "passive"))
      (node (ref "U$1") (pin "18") (pinfunction "18/A4/SDA0_18") (pintype "bidirectional"))
    )
    (net (code "20") (name "/DIR_Y") (class "Default")
      (node (ref "DRV_Y") (pin "9") (pinfunction "DIR_9") (pintype "input"))
      (node (ref "J10") (pin "11") (pinfunction "11_11") (pintype "passive"))
      (node (ref "J10") (pin "12") (pinfunction "12_12") (pintype "passive"))
      (node (ref "U$1") (pin "38") (pinfunction "38/A14_38") (pintype "bidirectional"))
    )
    (net (code "21") (name "/DIR_Z") (class "Default")
      (node (ref "DRV_Z") (pin "9") (pinfunction "DIR_9") (pintype "input"))
      (node (ref "J10") (pin "7") (pinfunction "7_7") (pintype "passive"))
      (node (ref "J10") (pin "8") (pinfunction "8_8") (pintype "passive"))
      (node (ref "U$1") (pin "36") (pinfunction "36_36") (pintype "bidirectional"))
    )
    (net (code "22") (name "/ENCA") (class "Default")
      (node (ref "J9") (pin "17") (pinfunction "17_17") (pintype "passive"))
      (node (ref "J9") (pin "18") (pinfunction "18_18") (pintype "passive"))
      (node (ref "S1") (pin "A") (pinfunction "A_A") (pintype "bidirectional"))
      (node (ref "U$1") (pin "21") (pinfunction "21/A7_21") (pintype "bidirectional"))
    )
    (net (code "23") (name "/ENCB") (class "Default")
      (node (ref "J9") (pin "19") (pinfunction "19_19") (pintype "passive"))
      (node (ref "J9") (pin "20") (pinfunction "20_20") (pintype "passive"))
      (node (ref "S1") (pin "B") (pinfunction "B_B") (pintype "bidirectional"))
      (node (ref "U$1") (pin "22") (pinfunction "22/A8_22") (pintype "bidirectional"))
    )
    (net (code "24") (name "/EN_X") (class "Default")
      (node (ref "DRV_X") (pin "16") (pinfunction "~{EN}_16") (pintype "input"))
      (node (ref "J2") (pin "1") (pinfunction "1_1") (pintype "passive"))
      (node (ref "J2") (pin "2") (pinfunction "2_2") (pintype "passive"))
      (node (ref "U$1") (pin "23") (pinfunction "23/A9_23") (pintype "bidirectional"))
    )
    (net (code "25") (name "/EN_Y") (class "Default")
      (node (ref "DRV_Y") (pin "16") (pinfunction "~{EN}_16") (pintype "input"))
      (node (ref "J9") (pin "5") (pinfunction "5_5") (pintype "passive"))
      (node (ref "J9") (pin "6") (pinfunction "6_6") (pintype "passive"))
      (node (ref "U$1") (pin "15") (pinfunction "15/A1_15") (pintype "bidirectional"))
    )
    (net (code "26") (name "/EN_Z") (class "Default")
      (node (ref "DRV_Z") (pin "16") (pinfunction "~{EN}_16") (pintype "input"))
      (node (ref "J10") (pin "17") (pinfunction "17_17") (pintype "passive"))
      (node (ref "J10") (pin "18") (pinfunction "18_18") (pintype "passive"))
      (node (ref "U$1") (pin "41") (pinfunction "41/A17_41") (pintype "bidirectional"))
    )
    (net (code "27") (name "/LIM_X") (class "Default")
      (node (ref "C4") (pin "1") (pinfunction "1_1") (pintype "passive"))
      (node (ref "J8") (pin "13") (pinfunction "13_13") (pintype "passive"))
      (node (ref "J8") (pin "14") (pinfunction "14_14") (pintype "passive"))
      (node (ref "LIM") (pin "3") (pinfunction "3_3") (pintype "passive"))
      (node (ref "R1") (pin "1") (pinfunction "1_1") (pintype "passive"))
      (node (ref "U$1") (pin "6") (pinfunction "6*_6") (pintype "bidirectional"))
    )
    (net (code "28") (name "/LIM_Z") (class "Default")
      (node (ref "C3") (pin "1") (pinfunction "1_1") (pintype "passive"))
      (node (ref "J8") (pin "11") (pinfunction "11_11") (pintype "passive"))
      (node (ref "J8") (pin "12") (pinfunction "12_12") (pintype "passive"))
      (node (ref "LIM") (pin "1") (pinfunction "1_1") (pintype "passive"))
      (node (ref "R2") (pin "1") (pinfunction "1_1") (pintype "passive"))
      (node (ref "U$1") (pin "5") (pinfunction "5*_5") (pintype "bidirectional"))
    )
    (net (code "29") (name "/MISO") (class "Default")
      (node (ref "C18") (pin "2") (pinfunction "2_2") (pintype "passive"))
      (node (ref "R3") (pin "1") (pinfunction "1_1") (pintype "passive"))
      (node (ref "SEN0") (pin "6") (pinfunction "6_6") (pintype "passive"))
      (node (ref "SEN0-S") (pin "6") (pinfunction "6_6") (pintype "passive"))
      (node (ref "SEN1") (pin "6") (pinfunction "6_6") (pintype "passive"))
      (node (ref "SEN1-S") (pin "6") (pinfunction "6_6") (pintype "passive"))
      (node (ref "SEN2") (pin "6") (pinfunction "6_6") (pintype "passive"))
      (node (ref "SEN2-S") (pin "6") (pinfunction "6_6") (pintype "passive"))
      (node (ref "SEN3") (pin "6") (pinfunction "6_6") (pintype "passive"))
      (node (ref "SEN3-S") (pin "6") (pinfunction "6_6") (pintype "passive"))
    )
    (net (code "30") (name "/MISO_M") (class "Default")
      (node (ref "J8") (pin "25") (pinfunction "25_25") (pintype "passive"))
      (node (ref "J8") (pin "26") (pinfunction "26_26") (pintype "passive"))
      (node (ref "R3") (pin "2") (pinfunction "2_2") (pintype "passive"))
      (node (ref "U$1") (pin "12") (pinfunction "12/DIN_12") (pintype "bidirectional"))
    )
    (net (code "31") (name "/MOSI") (class "Default")
      (node (ref "C19") (pin "2") (pinfunction "2_2") (pintype "passive"))
      (node (ref "R4") (pin "1") (pinfunction "1_1") (pintype "passive"))
      (node (ref "SEN0") (pin "4") (pinfunction "4_4") (pintype "passive"))
      (node (ref "SEN0-S") (pin "4") (pinfunction "4_4") (pintype "passive"))
      (node (ref "SEN1") (pin "4") (pinfunction "4_4") (pintype "passive"))
      (node (ref "SEN1-S") (pin "4") (pinfunction "4_4") (pintype "passive"))
      (node (ref "SEN2") (pin "4") (pinfunction "4_4") (pintype "passive"))
      (node (ref "SEN2-S") (pin "4") (pinfunction "4_4") (pintype "passive"))
      (node (ref "SEN3") (pin "4") (pinfunction "4_4") (pintype "passive"))
      (node (ref "SEN3-S") (pin "4") (pinfunction "4_4") (pintype "passive"))
    )
    (net (code "32") (name "/MOSI1") (class "Default")
      (node (ref "C25") (pin "2") (pinfunction "2_2") (pintype "passive"))
      (node (ref "DISPLAY") (pin "3") (pinfunction "3_3") (pintype "passive"))
      (node (ref "R20") (pin "1") (pinfunction "1_1") (pintype "passive"))
    )
    (net (code "33") (name "/MOSI1_M") (class "Default")
      (node (ref "J11") (pin "5") (pinfunction "5_5") (pintype "passive"))
      (node (ref "J11") (pin "6") (pinfunction "6_6") (pintype "passive"))
      (node (ref "R20") (pin "2") (pinfunction "2_2") (pintype "passive"))
      (node (ref "U$1") (pin "26") (pinfunction "26/A12_26") (pintype "bidirectional"))
    )
    (net (code "34") (name "/MOSI_M") (class "Default")
      (node (ref "J8") (pin "23") (pinfunction "23_23") (pintype "passive"))
      (node (ref "J8") (pin "24") (pinfunction "24_24") (pintype "passive"))
      (node (ref "R4") (pin "2") (pinfunction "2_2") (pintype "passive"))
      (node (ref "U$1") (pin "11") (pinfunction "11/DOUT_11") (pintype "bidirectional"))
    )
    (net (code "35") (name "/RST") (class "Default")
      (node (ref "DISPLAY") (pin "7") (pinfunction "7_7") (pintype "passive"))
      (node (ref "J11") (pin "3") (pinfunction "3_3") (pintype "passive"))
      (node (ref "J11") (pin "4") (pinfunction "4_4") (pintype "passive"))
      (node (ref "U$1") (pin "25") (pinfunction "25/A11_25") (pintype "bidirectional"))
    )
    (net (code "36") (name "/RX_X") (class "Default")
      (node (ref "DRV_X") (pin "13") (pinfunction "RX_13") (pintype "input"))
      (node (ref "DRV_Y") (pin "13") (pinfunction "RX_13") (pintype "input"))
      (node (ref "DRV_Z") (pin "13") (pinfunction "RX_13") (pintype "input"))
      (node (ref "J9") (pin "7") (pinfunction "7_7") (pintype "passive"))
      (node (ref "J9") (pin "8") (pinfunction "8_8") (pintype "passive"))
      (node (ref "R8") (pin "2") (pinfunction "2_2") (pintype "passive"))
      (node (ref "U$1") (pin "16") (pinfunction "16/A2_16") (pintype "bidirectional"))
    )
    (net (code "37") (name "/SCK") (class "Default")
      (node (ref "C20") (pin "2") (pinfunction "2_2") (pintype "passive"))
      (node (ref "R5") (pin "1") (pinfunction "1_1") (pintype "passive"))
      (node (ref "SEN0") (pin "2") (pinfunction "2_2") (pintype "passive"))
      (node (ref "SEN0-S") (pin "2") (pinfunction "2_2") (pintype "passive"))
      (node (ref "SEN1") (pin "2") (pinfunction "2_2") (pintype "passive"))
      (node (ref "SEN1-S") (pin "2") (pinfunction "2_2") (pintype "passive"))
      (node (ref "SEN2") (pin "2") (pinfunction "2_2") (pintype "passive"))
      (node (ref "SEN2-S") (pin "2") (pinfunction "2_2") (pintype "passive"))
      (node (ref "SEN3") (pin "2") (pinfunction "2_2") (pintype "passive"))
      (node (ref "SEN3-S") (pin "2") (pinfunction "2_2") (pintype "passive"))
    )
    (net (code "38") (name "/SCK1") (class "Default")
      (node (ref "C26") (pin "2") (pinfunction "2_2") (pintype "passive"))
      (node (ref "DISPLAY") (pin "4") (pinfunction "4_4") (pintype "passive"))
      (node (ref "R21") (pin "1") (pinfunction "1_1") (pintype "passive"))
    )
    (net (code "39") (name "/SCK1_M") (class "Default")
      (node (ref "J11") (pin "7") (pinfunction "7_7") (pintype "passive"))
      (node (ref "J11") (pin "8") (pinfunction "8_8") (pintype "passive"))
      (node (ref "R21") (pin "2") (pinfunction "2_2") (pintype "passive"))
      (node (ref "U$1") (pin "27") (pinfunction "27/A13_27") (pintype "bidirectional"))
    )
    (net (code "40") (name "/SCK_M") (class "Default")
      (node (ref "J9") (pin "1") (pinfunction "1_1") (pintype "passive"))
      (node (ref "J9") (pin "2") (pinfunction "2_2") (pintype "passive"))
      (node (ref "R5") (pin "2") (pinfunction "2_2") (pintype "passive"))
      (node (ref "U$1") (pin "13") (pinfunction "13/SCK_13") (pintype "bidirectional"))
    )
    (net (code "41") (name "/STP_X") (class "Default")
      (node (ref "DRV_X") (pin "10") (pinfunction "STEP_10") (pintype "input"))
      (node (ref "J9") (pin "13") (pinfunction "13_13") (pintype "passive"))
      (node (ref "J9") (pin "14") (pinfunction "14_14") (pintype "passive"))
      (node (ref "U$1") (pin "19") (pinfunction "19/A5/SCL0_19") (pintype "bidirectional"))
    )
    (net (code "42") (name "/STP_Y") (class "Default")
      (node (ref "DRV_Y") (pin "10") (pinfunction "STEP_10") (pintype "input"))
      (node (ref "J10") (pin "13") (pinfunction "13_13") (pintype "passive"))
      (node (ref "J10") (pin "14") (pinfunction "14_14") (pintype "passive"))
      (node (ref "U$1") (pin "39") (pinfunction "39/A15_39") (pintype "bidirectional"))
    )
    (net (code "43") (name "/STP_Z") (class "Default")
      (node (ref "DRV_Z") (pin "10") (pinfunction "STEP_10") (pintype "input"))
      (node (ref "J10") (pin "1") (pinfunction "1_1") (pintype "passive"))
      (node (ref "J10") (pin "2") (pinfunction "2_2") (pintype "passive"))
      (node (ref "U$1") (pin "33") (pinfunction "33_33") (pintype "bidirectional"))
    )
    (net (code "44") (name "GND") (class "Default")
      (node (ref "24V_IN") (pin "1") (pinfunction "1_1") (pintype "passive"))
      (node (ref "5V_IN") (pin "1") (pinfunction "1_1") (pintype "passive"))
      (node (ref "BUTT_HAND") (pin "2") (pinfunction "2_2") (pintype "passive"))
      (node (ref "BUTT_HAND") (pin "4") (pinfunction "4_4") (pintype "passive"))
      (node (ref "C1") (pin "-") (pinfunction "-_-") (pintype "passive"))
      (node (ref "C10") (pin "2") (pinfunction "2_2") (pintype "passive"))
      (node (ref "C11") (pin "2") (pinfunction "2_2") (pintype "passive"))
      (node (ref "C12") (pin "-") (pinfunction "-_-") (pintype "passive"))
      (node (ref "C13") (pin "-") (pinfunction "-_-") (pintype "passive"))
      (node (ref "C14") (pin "2") (pinfunction "2_2") (pintype "passive"))
      (node (ref "C15") (pin "2") (pinfunction "2_2") (pintype "passive"))
      (node (ref "C16") (pin "2") (pinfunction "2_2") (pintype "passive"))
      (node (ref "C17") (pin "2") (pinfunction "2_2") (pintype "passive"))
      (node (ref "C18") (pin "1") (pinfunction "1_1") (pintype "passive"))
      (node (ref "C19") (pin "1") (pinfunction "1_1") (pintype "passive"))
      (node (ref "C2") (pin "-") (pinfunction "-_-") (pintype "passive"))
      (node (ref "C20") (pin "1") (pinfunction "1_1") (pintype "passive"))
      (node (ref "C21") (pin "1") (pinfunction "1_1") (pintype "passive"))
      (node (ref "C22") (pin "1") (pinfunction "1_1") (pintype "passive"))
      (node (ref "C23") (pin "1") (pinfunction "1_1") (pintype "passive"))
      (node (ref "C24") (pin "1") (pinfunction "1_1") (pintype "passive"))
      (node (ref "C25") (pin "1") (pinfunction "1_1") (pintype "passive"))
      (node (ref "C26") (pin "1") (pinfunction "1_1") (pintype "passive"))
      (node (ref "C27") (pin "1") (pinfunction "1_1") (pintype "passive"))
      (node (ref "C3") (pin "2") (pinfunction "2_2") (pintype "passive"))
      (node (ref "C4") (pin "2") (pinfunction "2_2") (pintype "passive"))
      (node (ref "C5") (pin "2") (pinfunction "2_2") (pintype "passive"))
      (node (ref "C6") (pin "2") (pinfunction "2_2") (pintype "passive"))
      (node (ref "C7") (pin "2") (pinfunction "2_2") (pintype "passive"))
      (node (ref "C8") (pin "2") (pinfunction "2_2") (pintype "passive"))
      (node (ref "CR1") (pin "2") (pinfunction "2_2") (pintype "passive"))
      (node (ref "DISPLAY") (pin "2") (pinfunction "2_2") (pintype "passive"))
      (node (ref "DRV_X") (pin "1") (pinfunction "GND_1") (pintype "power_in"))
      (node (ref "DRV_X") (pin "14") (pinfunction "MS2_14") (pintype "input"))
      (node (ref "DRV_X") (pin "15") (pinfunction "MS1_15") (pintype "input"))
      (node (ref "DRV_X") (pin "7") (pinfunction "GND_7") (pintype "power_in"))
      (node (ref "DRV_Y") (pin "1") (pinfunction "GND_1") (pintype "power_in"))
      (node (ref "DRV_Y") (pin "14") (pinfunction "MS2_14") (pintype "input"))
      (node (ref "DRV_Y") (pin "7") (pinfunction "GND_7") (pintype "power_in"))
      (node (ref "DRV_Z") (pin "1") (pinfunction "GND_1") (pintype "power_in"))
      (node (ref "DRV_Z") (pin "15") (pinfunction "MS1_15") (pintype "input"))
      (node (ref "DRV_Z") (pin "7") (pinfunction "GND_7") (pintype "power_in"))
      (node (ref "GND") (pin "1") (pinfunction "1_1") (pintype "passive"))
      (node (ref "GND") (pin "2") (pinfunction "2_2") (pintype "passive"))
      (node (ref "GND") (pin "3") (pinfunction "3_3") (pintype "passive"))
      (node (ref "GND") (pin "4") (pinfunction "4_4") (pintype "passive"))
      (node (ref "GND") (pin "5") (pinfunction "5_5") (pintype "passive"))
      (node (ref "J10") (pin "19") (pinfunction "19_19") (pintype "passive"))
      (node (ref "J10") (pin "20") (pinfunction "20_20") (pintype "passive"))
      (node (ref "LIM") (pin "2") (pinfunction "2_2") (pintype "passive"))
      (node (ref "LIM") (pin "4") (pinfunction "4_4") (pintype "passive"))
      (node (ref "R23") (pin "1") (pinfunction "1_1") (pintype "passive"))
      (node (ref "R25") (pin "1") (pinfunction "1_1") (pintype "passive"))
      (node (ref "S1") (pin "C") (pinfunction "C_C") (pintype "bidirectional"))
      (node (ref "S1") (pin "SW-") (pinfunction "SW-_SW-") (pintype "bidirectional"))
      (node (ref "SEN0") (pin "3") (pinfunction "3_3") (pintype "passive"))
      (node (ref "SEN0") (pin "5") (pinfunction "5_5") (pintype "passive"))
      (node (ref "SEN0") (pin "7") (pinfunction "7_7") (pintype "passive"))
      (node (ref "SEN0") (pin "P1") (pinfunction "SHIELD_P1") (pintype "passive"))
      (node (ref "SEN0") (pin "P2") (pinfunction "SHIELD_P2") (pintype "passive"))
      (node (ref "SEN0-S") (pin "3") (pinfunction "3_3") (pintype "passive"))
      (node (ref "SEN0-S") (pin "5") (pinfunction "5_5") (pintype "passive"))
      (node (ref "SEN0-S") (pin "7") (pinfunction "7_7") (pintype "passive"))
      (node (ref "SEN1") (pin "3") (pinfunction "3_3") (pintype "passive"))
      (node (ref "SEN1") (pin "5") (pinfunction "5_5") (pintype "passive"))
      (node (ref "SEN1") (pin "7") (pinfunction "7_7") (pintype "passive"))
      (node (ref "SEN1") (pin "P1") (pinfunction "SHIELD_P1") (pintype "passive"))
      (node (ref "SEN1") (pin "P2") (pinfunction "SHIELD_P2") (pintype "passive"))
      (node (ref "SEN1-S") (pin "3") (pinfunction "3_3") (pintype "passive"))
      (node (ref "SEN1-S") (pin "5") (pinfunction "5_5") (pintype "passive"))
      (node (ref "SEN1-S") (pin "7") (pinfunction "7_7") (pintype "passive"))
      (node (ref "SEN2") (pin "3") (pinfunction "3_3") (pintype "passive"))
      (node (ref "SEN2") (pin "5") (pinfunction "5_5") (pintype "passive"))
      (node (ref "SEN2") (pin "7") (pinfunction "7_7") (pintype "passive"))
      (node (ref "SEN2") (pin "P1") (pinfunction "SHIELD_P1") (pintype "passive"))
      (node (ref "SEN2") (pin "P2") (pinfunction "SHIELD_P2") (pintype "passive"))
      (node (ref "SEN2-S") (pin "3") (pinfunction "3_3") (pintype "passive"))
      (node (ref "SEN2-S") (pin "5") (pinfunction "5_5") (pintype "passive"))
      (node (ref "SEN2-S") (pin "7") (pinfunction "7_7") (pintype "passive"))
      (node (ref "SEN3") (pin "3") (pinfunction "3_3") (pintype "passive"))
      (node (ref "SEN3") (pin "5") (pinfunction "5_5") (pintype "passive"))
      (node (ref "SEN3") (pin "7") (pinfunction "7_7") (pintype "passive"))
      (node (ref "SEN3") (pin "P1") (pinfunction "SHIELD_P1") (pintype "passive"))
      (node (ref "SEN3") (pin "P2") (pinfunction "SHIELD_P2") (pintype "passive"))
      (node (ref "SEN3-S") (pin "3") (pinfunction "3_3") (pintype "passive"))
      (node (ref "SEN3-S") (pin "5") (pinfunction "5_5") (pintype "passive"))
      (node (ref "SEN3-S") (pin "7") (pinfunction "7_7") (pintype "passive"))
      (node (ref "U$1") (pin "GND1") (pinfunction "GND1_GND1") (pintype "power_in"))
      (node (ref "U$1") (pin "GND2") (pinfunction "GND2_GND2") (pintype "power_in"))
      (node (ref "U1") (pin "7") (pinfunction "GND_7") (pintype "power_in"))
      (node (ref "U1") (pin "EPAD") (pinfunction "EPAD_EPAD") (pintype "passive"))
    )
    (net (code "45") (name "Net-(C7-Pad1)") (class "Default")
      (node (ref "C7") (pin "1") (pinfunction "1_1") (pintype "passive"))
      (node (ref "R24") (pin "1") (pinfunction "1_1") (pintype "passive"))
    )
    (net (code "46") (name "Net-(DRV_X-M1A)") (class "Default")
      (node (ref "DRV_X") (pin "5") (pinfunction "M1A_5") (pintype "output"))
      (node (ref "U$2") (pin "3") (pinfunction "3_3") (pintype "bidirectional"))
    )
    (net (code "47") (name "Net-(DRV_X-M1B)") (class "Default")
      (node (ref "DRV_X") (pin "4") (pinfunction "M1B_4") (pintype "output"))
      (node (ref "U$2") (pin "2") (pinfunction "2_2") (pintype "bidirectional"))
    )
    (net (code "48") (name "Net-(DRV_X-M2A)") (class "Default")
      (node (ref "DRV_X") (pin "6") (pinfunction "M2A_6") (pintype "output"))
      (node (ref "U$2") (pin "4") (pinfunction "4_4") (pintype "bidirectional"))
    )
    (net (code "49") (name "Net-(DRV_X-M2B)") (class "Default")
      (node (ref "DRV_X") (pin "3") (pinfunction "M2B_3") (pintype "output"))
      (node (ref "U$2") (pin "1") (pinfunction "1_1") (pintype "bidirectional"))
    )
    (net (code "50") (name "Net-(DRV_Y-M1A)") (class "Default")
      (node (ref "DRV_Y") (pin "5") (pinfunction "M1A_5") (pintype "output"))
      (node (ref "U$3") (pin "3") (pinfunction "3_3") (pintype "bidirectional"))
    )
    (net (code "51") (name "Net-(DRV_Y-M1B)") (class "Default")
      (node (ref "DRV_Y") (pin "4") (pinfunction "M1B_4") (pintype "output"))
      (node (ref "U$3") (pin "2") (pinfunction "2_2") (pintype "bidirectional"))
    )
    (net (code "52") (name "Net-(DRV_Y-M2A)") (class "Default")
      (node (ref "DRV_Y") (pin "6") (pinfunction "M2A_6") (pintype "output"))
      (node (ref "U$3") (pin "4") (pinfunction "4_4") (pintype "bidirectional"))
    )
    (net (code "53") (name "Net-(DRV_Y-M2B)") (class "Default")
      (node (ref "DRV_Y") (pin "3") (pinfunction "M2B_3") (pintype "output"))
      (node (ref "U$3") (pin "1") (pinfunction "1_1") (pintype "bidirectional"))
    )
    (net (code "54") (name "Net-(DRV_Z-M1A)") (class "Default")
      (node (ref "DRV_Z") (pin "5") (pinfunction "M1A_5") (pintype "output"))
      (node (ref "U$4") (pin "3") (pinfunction "3_3") (pintype "bidirectional"))
    )
    (net (code "55") (name "Net-(DRV_Z-M1B)") (class "Default")
      (node (ref "DRV_Z") (pin "4") (pinfunction "M1B_4") (pintype "output"))
      (node (ref "U$4") (pin "2") (pinfunction "2_2") (pintype "bidirectional"))
    )
    (net (code "56") (name "Net-(DRV_Z-M2A)") (class "Default")
      (node (ref "DRV_Z") (pin "6") (pinfunction "M2A_6") (pintype "output"))
      (node (ref "U$4") (pin "4") (pinfunction "4_4") (pintype "bidirectional"))
    )
    (net (code "57") (name "Net-(DRV_Z-M2B)") (class "Default")
      (node (ref "DRV_Z") (pin "3") (pinfunction "M2B_3") (pintype "output"))
      (node (ref "U$4") (pin "1") (pinfunction "1_1") (pintype "bidirectional"))
    )
    (net (code "58") (name "Net-(J1-Pad1)") (class "Default")
      (node (ref "J1") (pin "1") (pinfunction "1_1") (pintype "passive"))
      (node (ref "J1") (pin "2") (pinfunction "2_2") (pintype "passive"))
      (node (ref "U$1") (pin "AGND") (pinfunction "AGND_AGND") (pintype "power_in"))
    )
    (net (code "59") (name "Net-(J10-Pad3)") (class "Default")
      (node (ref "J10") (pin "3") (pinfunction "3_3") (pintype "passive"))
      (node (ref "J10") (pin "4") (pinfunction "4_4") (pintype "passive"))
      (node (ref "U$1") (pin "34") (pinfunction "34_34") (pintype "bidirectional"))
    )
    (net (code "60") (name "Net-(J10-Pad5)") (class "Default")
      (node (ref "J10") (pin "5") (pinfunction "5_5") (pintype "passive"))
      (node (ref "J10") (pin "6") (pinfunction "6_6") (pintype "passive"))
      (node (ref "U$1") (pin "35") (pinfunction "35_35") (pintype "bidirectional"))
    )
    (net (code "61") (name "Net-(J10-Pad10)") (class "Default")
      (node (ref "J10") (pin "10") (pinfunction "10_10") (pintype "passive"))
      (node (ref "J10") (pin "9") (pinfunction "9_9") (pintype "passive"))
      (node (ref "U$1") (pin "37") (pinfunction "37_37") (pintype "bidirectional"))
    )
    (net (code "62") (name "Net-(U$1-0{slash}RX1)") (class "Default")
      (node (ref "J8") (pin "1") (pinfunction "1_1") (pintype "passive"))
      (node (ref "J8") (pin "2") (pinfunction "2_2") (pintype "passive"))
      (node (ref "U$1") (pin "0") (pinfunction "0/RX1_0") (pintype "bidirectional"))
    )
    (net (code "63") (name "Net-(U$1-1{slash}TX1)") (class "Default")
      (node (ref "J8") (pin "3") (pinfunction "3_3") (pintype "passive"))
      (node (ref "J8") (pin "4") (pinfunction "4_4") (pintype "passive"))
      (node (ref "U$1") (pin "1") (pinfunction "1/TX1_1") (pintype "bidirectional"))
    )
    (net (code "64") (name "Net-(U$1-7{slash}RX3)") (class "Default")
      (node (ref "J8") (pin "15") (pinfunction "15_15") (pintype "passive"))
      (node (ref "J8") (pin "16") (pinfunction "16_16") (pintype "passive"))
      (node (ref "U$1") (pin "7") (pinfunction "7/RX3_7") (pintype "bidirectional"))
    )
    (net (code "65") (name "Net-(U$1-8{slash}TX3)") (class "Default")
      (node (ref "J8") (pin "17") (pinfunction "17_17") (pintype "passive"))
      (node (ref "J8") (pin "18") (pinfunction "18_18") (pintype "passive"))
      (node (ref "U$1") (pin "8") (pinfunction "8/TX3_8") (pintype "bidirectional"))
    )
    (net (code "66") (name "Net-(U$1-9*{slash}RX2)") (class "Default")
      (node (ref "J8") (pin "19") (pinfunction "19_19") (pintype "passive"))
      (node (ref "J8") (pin "20") (pinfunction "20_20") (pintype "passive"))
      (node (ref "U$1") (pin "9") (pinfunction "9*/RX2_9") (pintype "bidirectional"))
    )
    (net (code "67") (name "Net-(U$1-14{slash}A0)") (class "Default")
      (node (ref "J9") (pin "3") (pinfunction "3_3") (pintype "passive"))
      (node (ref "J9") (pin "4") (pinfunction "4_4") (pintype "passive"))
      (node (ref "U$1") (pin "14") (pinfunction "14/A0_14") (pintype "bidirectional"))
    )
    (net (code "68") (name "Net-(U$1-17{slash}A3)") (class "Default")
      (node (ref "J9") (pin "10") (pinfunction "10_10") (pintype "passive"))
      (node (ref "J9") (pin "9") (pinfunction "9_9") (pintype "passive"))
      (node (ref "R8") (pin "1") (pinfunction "1_1") (pintype "passive"))
      (node (ref "U$1") (pin "17") (pinfunction "17/A3_17") (pintype "bidirectional"))
    )
    (net (code "69") (name "Net-(U$1-20{slash}A6)") (class "Default")
      (node (ref "J9") (pin "15") (pinfunction "15_15") (pintype "passive"))
      (node (ref "J9") (pin "16") (pinfunction "16_16") (pintype "passive"))
      (node (ref "U$1") (pin "20") (pinfunction "20/A6_20") (pintype "bidirectional"))
    )
    (net (code "70") (name "Net-(U$1-40{slash}A16)") (class "Default")
      (node (ref "J10") (pin "15") (pinfunction "15_15") (pintype "passive"))
      (node (ref "J10") (pin "16") (pinfunction "16_16") (pintype "passive"))
      (node (ref "U$1") (pin "40") (pinfunction "40/A16_40") (pintype "bidirectional"))
    )
    (net (code "71") (name "Net-(U1-BOOT)") (class "Default")
      (node (ref "C9") (pin "1") (pinfunction "1_1") (pintype "passive"))
      (node (ref "U1") (pin "1") (pinfunction "BOOT_1") (pintype "output"))
    )
    (net (code "72") (name "Net-(U1-COMP)") (class "Default")
      (node (ref "C8") (pin "1") (pinfunction "1_1") (pintype "passive"))
      (node (ref "R24") (pin "2") (pinfunction "2_2") (pintype "passive"))
      (node (ref "U1") (pin "6") (pinfunction "COMP_6") (pintype "output"))
    )
    (net (code "73") (name "Net-(U1-FB)") (class "Default")
      (node (ref "R25") (pin "2") (pinfunction "2_2") (pintype "passive"))
      (node (ref "R26") (pin "1") (pinfunction "1_1") (pintype "passive"))
      (node (ref "U1") (pin "5") (pinfunction "FB_5") (pintype "input"))
    )
    (net (code "74") (name "Net-(U1-RT{slash}CLK)") (class "Default")
      (node (ref "R23") (pin "2") (pinfunction "2_2") (pintype "passive"))
      (node (ref "U1") (pin "4") (pinfunction "RT/CLK_4") (pintype "input"))
    )
    (net (code "75") (name "Net-(U1-SW)") (class "Default")
      (node (ref "C9") (pin "2") (pinfunction "2_2") (pintype "passive"))
      (node (ref "CR1") (pin "1") (pinfunction "1_1") (pintype "passive"))
      (node (ref "L1") (pin "1") (pinfunction "1_1") (pintype "passive"))
      (node (ref "U1") (pin "8") (pinfunction "SW_8") (pintype "input"))
    )
    (net (code "76") (name "unconnected-(DRV_X-CLK-Pad11)") (class "Default")
      (node (ref "DRV_X") (pin "11") (pinfunction "CLK_11") (pintype "bidirectional"))
    )
    (net (code "77") (name "unconnected-(DRV_X-DIAG-Pad18)") (class "Default")
      (node (ref "DRV_X") (pin "18") (pinfunction "DIAG_18") (pintype "output"))
    )
    (net (code "78") (name "unconnected-(DRV_X-INDEX-Pad17)") (class "Default")
      (node (ref "DRV_X") (pin "17") (pinfunction "INDEX_17") (pintype "output"))
    )
    (net (code "79") (name "unconnected-(DRV_X-TX-Pad12)") (class "Default")
      (node (ref "DRV_X") (pin "12") (pinfunction "TX_12") (pintype "bidirectional"))
    )
    (net (code "80") (name "unconnected-(DRV_Y-CLK-Pad11)") (class "Default")
      (node (ref "DRV_Y") (pin "11") (pinfunction "CLK_11") (pintype "bidirectional"))
    )
    (net (code "81") (name "unconnected-(DRV_Y-DIAG-Pad18)") (class "Default")
      (node (ref "DRV_Y") (pin "18") (pinfunction "DIAG_18") (pintype "output"))
    )
    (net (code "82") (name "unconnected-(DRV_Y-INDEX-Pad17)") (class "Default")
      (node (ref "DRV_Y") (pin "17") (pinfunction "INDEX_17") (pintype "output"))
    )
    (net (code "83") (name "unconnected-(DRV_Y-TX-Pad12)") (class "Default")
      (node (ref "DRV_Y") (pin "12") (pinfunction "TX_12") (pintype "bidirectional"))
    )
    (net (code "84") (name "unconnected-(DRV_Z-CLK-Pad11)") (class "Default")
      (node (ref "DRV_Z") (pin "11") (pinfunction "CLK_11") (pintype "bidirectional"))
    )
    (net (code "85") (name "unconnected-(DRV_Z-DIAG-Pad18)") (class "Default")
      (node (ref "DRV_Z") (pin "18") (pinfunction "DIAG_18") (pintype "output"))
    )
    (net (code "86") (name "unconnected-(DRV_Z-INDEX-Pad17)") (class "Default")
      (node (ref "DRV_Z") (pin "17") (pinfunction "INDEX_17") (pintype "output"))
    )
    (net (code "87") (name "unconnected-(DRV_Z-TX-Pad12)") (class "Default")
      (node (ref "DRV_Z") (pin "12") (pinfunction "TX_12") (pintype "bidirectional"))
    )
    (net (code "88") (name "unconnected-(U1-EN-Pad3)") (class "Default")
      (node (ref "U1") (pin "3") (pinfunction "EN_3") (pintype "input"))
    )
  )
)
